# SSOP-TSSOP14.net
KiCad netlist of a schematic drawn in Altium Designer
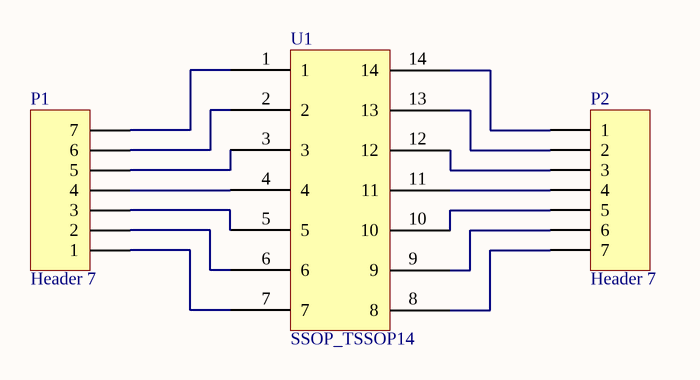
[diagram p0: SSOP-TSSOP14.SchDoc]

(export (version "E")
  (design (tool "Eeschema 10.0.6"))
  (components
    (comp (ref "P1")
      (value "Header 7")
      (footprint "HDR1X7")
      (description "Header, 7-Pin")
      (fields (field (name "PUBLISHER") "Altium Limited"))
      (libsource (lib "") (part "Header 7_1"))
    )
    (comp (ref "P2")
      (value "Header 7")
      (footprint "HDR1X7")
      (description "Header, 7-Pin")
      (fields (field (name "PUBLISHER") "Altium Limited"))
      (libsource (lib "Miscellaneous Connectors") (part "Header 7"))
    )
    (comp (ref "U1")
      (value "SSOP_TSSOP14")
      (footprint "SSOP-TSSOP14")
      (libsource (lib "PCB_Breakout_Boards") (part "SSOP_TSSOP14"))
    )
  )
  (nets
    (net (code "1") (name "Net-(P1-Pad1)") (class "Default")
      (node (ref "P1") (pin "1") (pinfunction "1_1") (pintype "passive"))
      (node (ref "U1") (pin "7") (pinfunction "7_7") (pintype "passive"))
    )
    (net (code "2") (name "Net-(P1-Pad2)") (class "Default")
      (node (ref "P1") (pin "2") (pinfunction "2_2") (pintype "passive"))
      (node (ref "U1") (pin "6") (pinfunction "6_6") (pintype "passive"))
    )
    (net (code "3") (name "Net-(P1-Pad3)") (class "Default")
      (node (ref "P1") (pin "3") (pinfunction "3_3") (pintype "passive"))
      (node (ref "U1") (pin "5") (pinfunction "5_5") (pintype "passive"))
    )
    (net (code "4") (name "Net-(P1-Pad4)") (class "Default")
      (node (ref "P1") (pin "4") (pinfunction "4_4") (pintype "passive"))
      (node (ref "U1") (pin "4") (pinfunction "4_4") (pintype "passive"))
    )
    (net (code "5") (name "Net-(P1-Pad5)") (class "Default")
      (node (ref "P1") (pin "5") (pinfunction "5_5") (pintype "passive"))
      (node (ref "U1") (pin "3") (pinfunction "3_3") (pintype "passive"))
    )
    (net (code "6") (name "Net-(P1-Pad6)") (class "Default")
      (node (ref "P1") (pin "6") (pinfunction "6_6") (pintype "passive"))
      (node (ref "U1") (pin "2") (pinfunction "2_2") (pintype "passive"))
    )
    (net (code "7") (name "Net-(P1-Pad7)") (class "Default")
      (node (ref "P1") (pin "7") (pinfunction "7_7") (pintype "passive"))
      (node (ref "U1") (pin "1") (pinfunction "1_1") (pintype "passive"))
    )
    (net (code "8") (name "Net-(P2-Pad1)") (class "Default")
      (node (ref "P2") (pin "1") (pinfunction "1_1") (pintype "passive"))
      (node (ref "U1") (pin "14") (pinfunction "14_14") (pintype "passive"))
    )
    (net (code "9") (name "Net-(P2-Pad2)") (class "Default")
      (node (ref "P2") (pin "2") (pinfunction "2_2") (pintype "passive"))
      (node (ref "U1") (pin "13") (pinfunction "13_13") (pintype "passive"))
    )
    (net (code "10") (name "Net-(P2-Pad3)") (class "Default")
      (node (ref "P2") (pin "3") (pinfunction "3_3") (pintype "passive"))
      (node (ref "U1") (pin "12") (pinfunction "12_12") (pintype "passive"))
    )
    (net (code "11") (name "Net-(P2-Pad4)") (class "Default")
      (node (ref "P2") (pin "4") (pinfunction "4_4") (pintype "passive"))
      (node (ref "U1") (pin "11") (pinfunction "11_11") (pintype "passive"))
    )
    (net (code "12") (name "Net-(P2-Pad5)") (class "Default")
      (node (ref "P2") (pin "5") (pinfunction "5_5") (pintype "passive"))
      (node (ref "U1") (pin "10") (pinfunction "10_10") (pintype "passive"))
    )
    (net (code "13") (name "Net-(P2-Pad6)") (class "Default")
      (node (ref "P2") (pin "6") (pinfunction "6_6") (pintype "passive"))
      (node (ref "U1") (pin "9") (pinfunction "9_9") (pintype "passive"))
    )
    (net (code "14") (name "Net-(P2-Pad7)") (class "Default")
      (node (ref "P2") (pin "7") (pinfunction "7_7") (pintype "passive"))
      (node (ref "U1") (pin "8") (pinfunction "8_8") (pintype "passive"))
    )
  )
)
